# LMP9100_v2_3.net
KiCad netlist of a schematic drawn in EAGLE
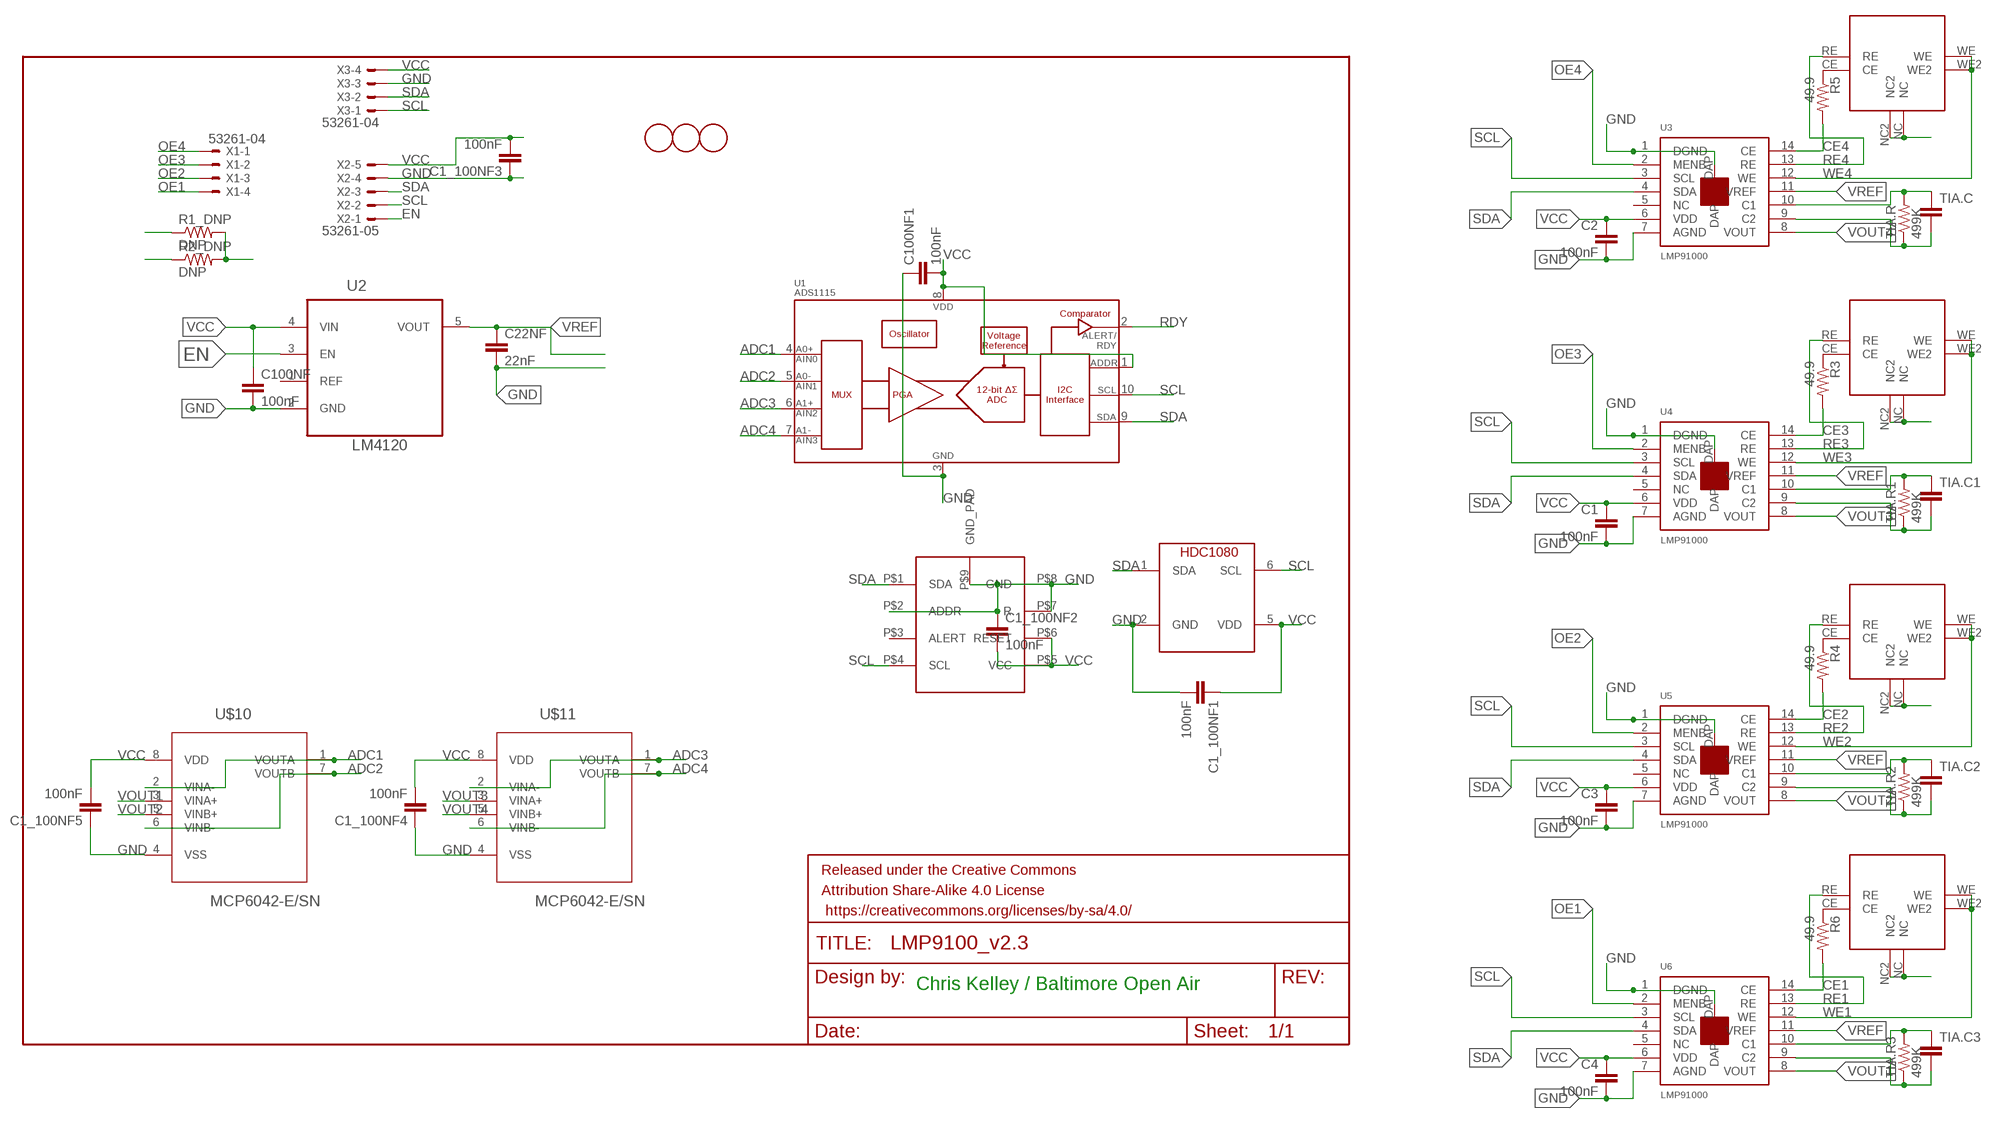
[diagram p0: schematic, sheet 1]

(export (version "E")
  (design (tool "Eeschema 10.0.6"))
  (components
    (comp (ref "C1")
      (value "100nF")
      (footprint "eagle-import:0603-CAP")
      (libsource (lib "eagle-import") (part "CAP0603-CAP"))
    )
    (comp (ref "C1_100NF1")
      (value "100nF")
      (footprint "eagle-import:0603-CAP")
      (libsource (lib "eagle-import") (part "CAP0603-CAP"))
    )
    (comp (ref "C1_100NF2")
      (value "100nF")
      (footprint "eagle-import:0603-CAP")
      (libsource (lib "eagle-import") (part "CAP0603-CAP"))
    )
    (comp (ref "C1_100NF3")
      (value "100nF")
      (footprint "eagle-import:0603-CAP")
      (libsource (lib "eagle-import") (part "CAP0603-CAP"))
    )
    (comp (ref "C1_100NF4")
      (value "100nF")
      (footprint "eagle-import:0603-CAP")
      (libsource (lib "eagle-import") (part "CAP0603-CAP"))
    )
    (comp (ref "C1_100NF5")
      (value "100nF")
      (footprint "eagle-import:0603-CAP")
      (libsource (lib "eagle-import") (part "CAP0603-CAP"))
    )
    (comp (ref "C2")
      (value "100nF")
      (footprint "eagle-import:0603-CAP")
      (libsource (lib "eagle-import") (part "CAP0603-CAP"))
    )
    (comp (ref "C3")
      (value "100nF")
      (footprint "eagle-import:0603-CAP")
      (libsource (lib "eagle-import") (part "CAP0603-CAP"))
    )
    (comp (ref "C4")
      (value "100nF")
      (footprint "eagle-import:0603-CAP")
      (libsource (lib "eagle-import") (part "CAP0603-CAP"))
    )
    (comp (ref "C22NF")
      (value "22nF")
      (footprint "eagle-import:0603-CAP")
      (libsource (lib "eagle-import") (part "CAP0603-CAP"))
    )
    (comp (ref "C100NF")
      (value "100nF")
      (footprint "eagle-import:0603-CAP")
      (libsource (lib "eagle-import") (part "CAP0603-CAP"))
    )
    (comp (ref "C100NF1")
      (value "100nF")
      (footprint "eagle-import:0603-CAP")
      (libsource (lib "eagle-import") (part "CAP0603-CAP"))
    )
    (comp (ref "FRAME1")
      (value "FRAME-LETTER")
      (footprint "eagle-import:CREATIVE_COMMONS")
      (libsource (lib "eagle-import") (part "FRAME-LETTER"))
    )
    (comp (ref "R1_DNP")
      (value "DNP")
      (footprint "eagle-import:0603-RES")
      (libsource (lib "eagle-import") (part "RESISTOR0603-RES"))
    )
    (comp (ref "R2_DNP")
      (value "DNP")
      (footprint "eagle-import:0603-RES")
      (libsource (lib "eagle-import") (part "RESISTOR0603-RES"))
    )
    (comp (ref "R3")
      (value "49.9")
      (footprint "eagle-import:0603-RES")
      (libsource (lib "eagle-import") (part "RESISTOR0603-RES"))
    )
    (comp (ref "R4")
      (value "49.9")
      (footprint "eagle-import:0603-RES")
      (libsource (lib "eagle-import") (part "RESISTOR0603-RES"))
    )
    (comp (ref "R5")
      (value "49.9")
      (footprint "eagle-import:0603-RES")
      (libsource (lib "eagle-import") (part "RESISTOR0603-RES"))
    )
    (comp (ref "R6")
      (value "49.9")
      (footprint "eagle-import:0603-RES")
      (libsource (lib "eagle-import") (part "RESISTOR0603-RES"))
    )
    (comp (ref "TIA.C")
      (value "CAP0603-CAP")
      (footprint "eagle-import:0603-CAP")
      (libsource (lib "eagle-import") (part "CAP0603-CAP"))
    )
    (comp (ref "TIA.C1")
      (value "CAP0603-CAP")
      (footprint "eagle-import:0603-CAP")
      (libsource (lib "eagle-import") (part "CAP0603-CAP"))
    )
    (comp (ref "TIA.C2")
      (value "CAP0603-CAP")
      (footprint "eagle-import:0603-CAP")
      (libsource (lib "eagle-import") (part "CAP0603-CAP"))
    )
    (comp (ref "TIA.C3")
      (value "CAP0603-CAP")
      (footprint "eagle-import:0603-CAP")
      (libsource (lib "eagle-import") (part "CAP0603-CAP"))
    )
    (comp (ref "TIA.R")
      (value "499K")
      (footprint "eagle-import:0603-RES")
      (libsource (lib "eagle-import") (part "RESISTOR0603-RES"))
    )
    (comp (ref "TIA.R1")
      (value "499K")
      (footprint "eagle-import:0603-RES")
      (libsource (lib "eagle-import") (part "RESISTOR0603-RES"))
    )
    (comp (ref "TIA.R2")
      (value "499K")
      (footprint "eagle-import:0603-RES")
      (libsource (lib "eagle-import") (part "RESISTOR0603-RES"))
    )
    (comp (ref "TIA.R3")
      (value "499K")
      (footprint "eagle-import:0603-RES")
      (libsource (lib "eagle-import") (part "RESISTOR0603-RES"))
    )
    (comp (ref "U$1")
      (value "FIDUCIAL")
      (footprint "eagle-import:FIDUCIAL_1MM")
      (libsource (lib "eagle-import") (part "FIDUCIAL"))
    )
    (comp (ref "U$2")
      (value "SHT31-D")
      (footprint "eagle-import:SHT31-D")
      (libsource (lib "eagle-import") (part "SHT31-D"))
    )
    (comp (ref "U$3")
      (value "HDC1080")
      (footprint "eagle-import:WSON-6-PAD")
      (libsource (lib "eagle-import") (part "HDC1080"))
    )
    (comp (ref "U$4")
      (value "SPEC-SENSOR")
      (footprint "eagle-import:SPEC-SENSOR")
      (libsource (lib "eagle-import") (part "SPEC-SENSOR"))
    )
    (comp (ref "U$5")
      (value "SPEC-SENSOR")
      (footprint "eagle-import:SPEC-SENSOR")
      (libsource (lib "eagle-import") (part "SPEC-SENSOR"))
    )
    (comp (ref "U$6")
      (value "FIDUCIAL")
      (footprint "eagle-import:FIDUCIAL_1MM")
      (libsource (lib "eagle-import") (part "FIDUCIAL"))
    )
    (comp (ref "U$7")
      (value "FIDUCIAL")
      (footprint "eagle-import:FIDUCIAL_1MM")
      (libsource (lib "eagle-import") (part "FIDUCIAL"))
    )
    (comp (ref "U$8")
      (value "SPEC-SENSOR")
      (footprint "eagle-import:SPEC-SENSOR")
      (libsource (lib "eagle-import") (part "SPEC-SENSOR"))
    )
    (comp (ref "U$9")
      (value "SPEC-SENSOR")
      (footprint "eagle-import:SPEC-SENSOR")
      (libsource (lib "eagle-import") (part "SPEC-SENSOR"))
    )
    (comp (ref "U$10")
      (value "MCP6042-E/SN")
      (footprint "eagle-import:SOIC127P600X175-8N")
      (fields (field (name "MF") "Microchip"))
      (libsource (lib "eagle-import") (part "MCP6042-E/SN"))
    )
    (comp (ref "U$11")
      (value "MCP6042-E/SN")
      (footprint "eagle-import:SOIC127P600X175-8N")
      (fields (field (name "MF") "Microchip"))
      (libsource (lib "eagle-import") (part "MCP6042-E/SN"))
    )
    (comp (ref "U1")
      (value "ADS1115")
      (footprint "eagle-import:MSOP10")
      (libsource (lib "eagle-import") (part "ADS1015"))
    )
    (comp (ref "U2")
      (value "LM4120")
      (footprint "eagle-import:SOT95P284X122-5N")
      (fields (field (name "MF") "Texas Instruments") (field (name "MP") "LM4120AIM5-2.5/NOPB"))
      (libsource (lib "eagle-import") (part "LM4120AIM5-2.5"))
    )
    (comp (ref "U3")
      (value "LMP91000")
      (footprint "eagle-import:LMP91000")
      (libsource (lib "eagle-import") (part "LMP91000"))
    )
    (comp (ref "U4")
      (value "LMP91000")
      (footprint "eagle-import:LMP91000")
      (libsource (lib "eagle-import") (part "LMP91000"))
    )
    (comp (ref "U5")
      (value "LMP91000")
      (footprint "eagle-import:LMP91000")
      (libsource (lib "eagle-import") (part "LMP91000"))
    )
    (comp (ref "U6")
      (value "LMP91000")
      (footprint "eagle-import:LMP91000")
      (libsource (lib "eagle-import") (part "LMP91000"))
    )
    (comp (ref "X1")
      (value "53261-04")
      (footprint "eagle-import:53261-04")
      (libsource (lib "eagle-import") (part "53?-04261"))
    )
    (comp (ref "X2")
      (value "53261-05")
      (footprint "eagle-import:53261-05")
      (libsource (lib "eagle-import") (part "53?-05261"))
    )
    (comp (ref "X3")
      (value "53261-04")
      (footprint "eagle-import:53261-04")
      (libsource (lib "eagle-import") (part "53?-04261"))
    )
  )
  (nets
    (net (code "1") (name "/ADC1") (class "Default")
      (node (ref "U$10") (pin "1") (pinfunction "VOUTA_1") (pintype "output"))
      (node (ref "U$10") (pin "2") (pinfunction "VINA-_2") (pintype "input"))
      (node (ref "U1") (pin "4") (pinfunction "AIN0_4") (pintype "bidirectional"))
    )
    (net (code "2") (name "/ADC2") (class "Default")
      (node (ref "U$10") (pin "6") (pinfunction "VINB-_6") (pintype "input"))
      (node (ref "U$10") (pin "7") (pinfunction "VOUTB_7") (pintype "output"))
      (node (ref "U1") (pin "5") (pinfunction "AIN1_5") (pintype "bidirectional"))
    )
    (net (code "3") (name "/ADC3") (class "Default")
      (node (ref "U$11") (pin "1") (pinfunction "VOUTA_1") (pintype "output"))
      (node (ref "U$11") (pin "2") (pinfunction "VINA-_2") (pintype "input"))
      (node (ref "U1") (pin "6") (pinfunction "AIN2_6") (pintype "bidirectional"))
    )
    (net (code "4") (name "/ADC4") (class "Default")
      (node (ref "U$11") (pin "6") (pinfunction "VINB-_6") (pintype "input"))
      (node (ref "U$11") (pin "7") (pinfunction "VOUTB_7") (pintype "output"))
      (node (ref "U1") (pin "7") (pinfunction "AIN3_7") (pintype "bidirectional"))
    )
    (net (code "5") (name "/CE1") (class "Default")
      (node (ref "R6") (pin "2") (pinfunction "2_2") (pintype "passive"))
      (node (ref "U6") (pin "14") (pinfunction "CE_14") (pintype "bidirectional"))
    )
    (net (code "6") (name "/CE2") (class "Default")
      (node (ref "R4") (pin "2") (pinfunction "2_2") (pintype "passive"))
      (node (ref "U5") (pin "14") (pinfunction "CE_14") (pintype "bidirectional"))
    )
    (net (code "7") (name "/CE3") (class "Default")
      (node (ref "R3") (pin "2") (pinfunction "2_2") (pintype "passive"))
      (node (ref "U4") (pin "14") (pinfunction "CE_14") (pintype "bidirectional"))
    )
    (net (code "8") (name "/CE4") (class "Default")
      (node (ref "R5") (pin "2") (pinfunction "2_2") (pintype "passive"))
      (node (ref "U3") (pin "14") (pinfunction "CE_14") (pintype "bidirectional"))
    )
    (net (code "9") (name "/RDY") (class "Default")
      (node (ref "U1") (pin "2") (pinfunction "ALERT/RDY_2") (pintype "bidirectional"))
    )
    (net (code "10") (name "/RE1") (class "Default")
      (node (ref "U$9") (pin "RE") (pinfunction "RE_RE") (pintype "bidirectional"))
      (node (ref "U6") (pin "13") (pinfunction "RE_13") (pintype "bidirectional"))
    )
    (net (code "11") (name "/RE2") (class "Default")
      (node (ref "U$8") (pin "RE") (pinfunction "RE_RE") (pintype "bidirectional"))
      (node (ref "U5") (pin "13") (pinfunction "RE_13") (pintype "bidirectional"))
    )
    (net (code "12") (name "/RE3") (class "Default")
      (node (ref "U$5") (pin "RE") (pinfunction "RE_RE") (pintype "bidirectional"))
      (node (ref "U4") (pin "13") (pinfunction "RE_13") (pintype "bidirectional"))
    )
    (net (code "13") (name "/RE4") (class "Default")
      (node (ref "U$4") (pin "RE") (pinfunction "RE_RE") (pintype "bidirectional"))
      (node (ref "U3") (pin "13") (pinfunction "RE_13") (pintype "bidirectional"))
    )
    (net (code "14") (name "/WE1") (class "Default")
      (node (ref "U$9") (pin "WE") (pinfunction "WE_WE") (pintype "bidirectional"))
      (node (ref "U$9") (pin "WE2") (pinfunction "WE2_WE2") (pintype "bidirectional"))
      (node (ref "U6") (pin "12") (pinfunction "WE_12") (pintype "bidirectional"))
    )
    (net (code "15") (name "/WE2") (class "Default")
      (node (ref "U$8") (pin "WE") (pinfunction "WE_WE") (pintype "bidirectional"))
      (node (ref "U$8") (pin "WE2") (pinfunction "WE2_WE2") (pintype "bidirectional"))
      (node (ref "U5") (pin "12") (pinfunction "WE_12") (pintype "bidirectional"))
    )
    (net (code "16") (name "/WE3") (class "Default")
      (node (ref "U$5") (pin "WE") (pinfunction "WE_WE") (pintype "bidirectional"))
      (node (ref "U$5") (pin "WE2") (pinfunction "WE2_WE2") (pintype "bidirectional"))
      (node (ref "U4") (pin "12") (pinfunction "WE_12") (pintype "bidirectional"))
    )
    (net (code "17") (name "/WE4") (class "Default")
      (node (ref "U$4") (pin "WE") (pinfunction "WE_WE") (pintype "bidirectional"))
      (node (ref "U$4") (pin "WE2") (pinfunction "WE2_WE2") (pintype "bidirectional"))
      (node (ref "U3") (pin "12") (pinfunction "WE_12") (pintype "bidirectional"))
    )
    (net (code "18") (name "EN") (class "Default")
      (node (ref "U2") (pin "3") (pinfunction "EN_3") (pintype "input"))
      (node (ref "X2") (pin "1") (pinfunction "S_1") (pintype "passive"))
    )
    (net (code "19") (name "GND") (class "Default")
      (node (ref "C1") (pin "2") (pinfunction "2_2") (pintype "passive"))
      (node (ref "C100NF") (pin "2") (pinfunction "2_2") (pintype "passive"))
      (node (ref "C100NF1") (pin "1") (pinfunction "1_1") (pintype "passive"))
      (node (ref "C1_100NF1") (pin "2") (pinfunction "2_2") (pintype "passive"))
      (node (ref "C1_100NF2") (pin "1") (pinfunction "1_1") (pintype "passive"))
      (node (ref "C1_100NF3") (pin "1") (pinfunction "1_1") (pintype "passive"))
      (node (ref "C1_100NF4") (pin "1") (pinfunction "1_1") (pintype "passive"))
      (node (ref "C1_100NF5") (pin "1") (pinfunction "1_1") (pintype "passive"))
      (node (ref "C2") (pin "2") (pinfunction "2_2") (pintype "passive"))
      (node (ref "C22NF") (pin "2") (pinfunction "2_2") (pintype "passive"))
      (node (ref "C3") (pin "2") (pinfunction "2_2") (pintype "passive"))
      (node (ref "C4") (pin "2") (pinfunction "2_2") (pintype "passive"))
      (node (ref "U$10") (pin "4") (pinfunction "VSS_4") (pintype "power_in"))
      (node (ref "U$11") (pin "4") (pinfunction "VSS_4") (pintype "power_in"))
      (node (ref "U$2") (pin "P$2") (pinfunction "ADDR_P$2") (pintype "bidirectional"))
      (node (ref "U$2") (pin "P$7") (pinfunction "R_P$7") (pintype "bidirectional"))
      (node (ref "U$2") (pin "P$8") (pinfunction "GND_P$8") (pintype "bidirectional"))
      (node (ref "U$2") (pin "P$9") (pinfunction "GND_PAD_P$9") (pintype "bidirectional"))
      (node (ref "U$3") (pin "2") (pinfunction "GND_2") (pintype "bidirectional"))
      (node (ref "U$4") (pin "NC") (pinfunction "NC_NC") (pintype "bidirectional"))
      (node (ref "U$4") (pin "NC2") (pinfunction "NC2_NC2") (pintype "bidirectional"))
      (node (ref "U$5") (pin "NC") (pinfunction "NC_NC") (pintype "bidirectional"))
      (node (ref "U$5") (pin "NC2") (pinfunction "NC2_NC2") (pintype "bidirectional"))
      (node (ref "U$8") (pin "NC") (pinfunction "NC_NC") (pintype "bidirectional"))
      (node (ref "U$8") (pin "NC2") (pinfunction "NC2_NC2") (pintype "bidirectional"))
      (node (ref "U$9") (pin "NC") (pinfunction "NC_NC") (pintype "bidirectional"))
      (node (ref "U$9") (pin "NC2") (pinfunction "NC2_NC2") (pintype "bidirectional"))
      (node (ref "U1") (pin "3") (pinfunction "VSS_3") (pintype "bidirectional"))
      (node (ref "U2") (pin "2") (pinfunction "GND_2") (pintype "passive"))
      (node (ref "U3") (pin "1") (pinfunction "DGND_1") (pintype "bidirectional"))
      (node (ref "U3") (pin "7") (pinfunction "AGND_7") (pintype "bidirectional"))
      (node (ref "U3") (pin "DAP") (pinfunction "DAP_DAP") (pintype "bidirectional"))
      (node (ref "U4") (pin "1") (pinfunction "DGND_1") (pintype "bidirectional"))
      (node (ref "U4") (pin "7") (pinfunction "AGND_7") (pintype "bidirectional"))
      (node (ref "U4") (pin "DAP") (pinfunction "DAP_DAP") (pintype "bidirectional"))
      (node (ref "U5") (pin "1") (pinfunction "DGND_1") (pintype "bidirectional"))
      (node (ref "U5") (pin "7") (pinfunction "AGND_7") (pintype "bidirectional"))
      (node (ref "U5") (pin "DAP") (pinfunction "DAP_DAP") (pintype "bidirectional"))
      (node (ref "U6") (pin "1") (pinfunction "DGND_1") (pintype "bidirectional"))
      (node (ref "U6") (pin "7") (pinfunction "AGND_7") (pintype "bidirectional"))
      (node (ref "U6") (pin "DAP") (pinfunction "DAP_DAP") (pintype "bidirectional"))
      (node (ref "X2") (pin "4") (pinfunction "S_4") (pintype "passive"))
      (node (ref "X3") (pin "3") (pinfunction "S_3") (pintype "passive"))
    )
    (net (code "20") (name "Net-(R3-Pad1)") (class "Default")
      (node (ref "R3") (pin "1") (pinfunction "1_1") (pintype "passive"))
      (node (ref "U$5") (pin "CE") (pinfunction "CE_CE") (pintype "bidirectional"))
    )
    (net (code "21") (name "Net-(R4-Pad1)") (class "Default")
      (node (ref "R4") (pin "1") (pinfunction "1_1") (pintype "passive"))
      (node (ref "U$8") (pin "CE") (pinfunction "CE_CE") (pintype "bidirectional"))
    )
    (net (code "22") (name "Net-(R5-Pad1)") (class "Default")
      (node (ref "R5") (pin "1") (pinfunction "1_1") (pintype "passive"))
      (node (ref "U$4") (pin "CE") (pinfunction "CE_CE") (pintype "bidirectional"))
    )
    (net (code "23") (name "Net-(R6-Pad1)") (class "Default")
      (node (ref "R6") (pin "1") (pinfunction "1_1") (pintype "passive"))
      (node (ref "U$9") (pin "CE") (pinfunction "CE_CE") (pintype "bidirectional"))
    )
    (net (code "24") (name "Net-(U3-C1)") (class "Default")
      (node (ref "TIA.C") (pin "1") (pinfunction "1_1") (pintype "passive"))
      (node (ref "TIA.R") (pin "2") (pinfunction "2_2") (pintype "passive"))
      (node (ref "U3") (pin "10") (pinfunction "C1_10") (pintype "bidirectional"))
    )
    (net (code "25") (name "Net-(U3-C2)") (class "Default")
      (node (ref "TIA.C") (pin "2") (pinfunction "2_2") (pintype "passive"))
      (node (ref "TIA.R") (pin "1") (pinfunction "1_1") (pintype "passive"))
      (node (ref "U3") (pin "9") (pinfunction "C2_9") (pintype "bidirectional"))
    )
    (net (code "26") (name "Net-(U4-C1)") (class "Default")
      (node (ref "TIA.C1") (pin "1") (pinfunction "1_1") (pintype "passive"))
      (node (ref "TIA.R1") (pin "2") (pinfunction "2_2") (pintype "passive"))
      (node (ref "U4") (pin "10") (pinfunction "C1_10") (pintype "bidirectional"))
    )
    (net (code "27") (name "Net-(U4-C2)") (class "Default")
      (node (ref "TIA.C1") (pin "2") (pinfunction "2_2") (pintype "passive"))
      (node (ref "TIA.R1") (pin "1") (pinfunction "1_1") (pintype "passive"))
      (node (ref "U4") (pin "9") (pinfunction "C2_9") (pintype "bidirectional"))
    )
    (net (code "28") (name "Net-(U5-C1)") (class "Default")
      (node (ref "TIA.C2") (pin "1") (pinfunction "1_1") (pintype "passive"))
      (node (ref "TIA.R2") (pin "2") (pinfunction "2_2") (pintype "passive"))
      (node (ref "U5") (pin "10") (pinfunction "C1_10") (pintype "bidirectional"))
    )
    (net (code "29") (name "Net-(U5-C2)") (class "Default")
      (node (ref "TIA.C2") (pin "2") (pinfunction "2_2") (pintype "passive"))
      (node (ref "TIA.R2") (pin "1") (pinfunction "1_1") (pintype "passive"))
      (node (ref "U5") (pin "9") (pinfunction "C2_9") (pintype "bidirectional"))
    )
    (net (code "30") (name "Net-(U6-C1)") (class "Default")
      (node (ref "TIA.C3") (pin "1") (pinfunction "1_1") (pintype "passive"))
      (node (ref "TIA.R3") (pin "2") (pinfunction "2_2") (pintype "passive"))
      (node (ref "U6") (pin "10") (pinfunction "C1_10") (pintype "bidirectional"))
    )
    (net (code "31") (name "Net-(U6-C2)") (class "Default")
      (node (ref "TIA.C3") (pin "2") (pinfunction "2_2") (pintype "passive"))
      (node (ref "TIA.R3") (pin "1") (pinfunction "1_1") (pintype "passive"))
      (node (ref "U6") (pin "9") (pinfunction "C2_9") (pintype "bidirectional"))
    )
    (net (code "32") (name "OE1") (class "Default")
      (node (ref "U6") (pin "2") (pinfunction "MENB_2") (pintype "bidirectional"))
      (node (ref "X1") (pin "4") (pinfunction "S_4") (pintype "passive"))
    )
    (net (code "33") (name "OE2") (class "Default")
      (node (ref "U5") (pin "2") (pinfunction "MENB_2") (pintype "bidirectional"))
      (node (ref "X1") (pin "3") (pinfunction "S_3") (pintype "passive"))
    )
    (net (code "34") (name "OE3") (class "Default")
      (node (ref "U4") (pin "2") (pinfunction "MENB_2") (pintype "bidirectional"))
      (node (ref "X1") (pin "2") (pinfunction "S_2") (pintype "passive"))
    )
    (net (code "35") (name "OE4") (class "Default")
      (node (ref "U3") (pin "2") (pinfunction "MENB_2") (pintype "bidirectional"))
      (node (ref "X1") (pin "1") (pinfunction "S_1") (pintype "passive"))
    )
    (net (code "36") (name "SCL") (class "Default")
      (node (ref "R1_DNP") (pin "1") (pinfunction "1_1") (pintype "passive"))
      (node (ref "U$2") (pin "P$4") (pinfunction "SCL_P$4") (pintype "bidirectional"))
      (node (ref "U$3") (pin "6") (pinfunction "SCL_6") (pintype "bidirectional"))
      (node (ref "U1") (pin "10") (pinfunction "SCL_10") (pintype "bidirectional"))
      (node (ref "U3") (pin "3") (pinfunction "SCL_3") (pintype "bidirectional"))
      (node (ref "U4") (pin "3") (pinfunction "SCL_3") (pintype "bidirectional"))
      (node (ref "U5") (pin "3") (pinfunction "SCL_3") (pintype "bidirectional"))
      (node (ref "U6") (pin "3") (pinfunction "SCL_3") (pintype "bidirectional"))
      (node (ref "X2") (pin "2") (pinfunction "S_2") (pintype "passive"))
      (node (ref "X3") (pin "1") (pinfunction "S_1") (pintype "passive"))
    )
    (net (code "37") (name "SDA") (class "Default")
      (node (ref "R2_DNP") (pin "1") (pinfunction "1_1") (pintype "passive"))
      (node (ref "U$2") (pin "P$1") (pinfunction "SDA_P$1") (pintype "bidirectional"))
      (node (ref "U$3") (pin "1") (pinfunction "SDA_1") (pintype "bidirectional"))
      (node (ref "U1") (pin "9") (pinfunction "SDA_9") (pintype "bidirectional"))
      (node (ref "U3") (pin "4") (pinfunction "SDA_4") (pintype "bidirectional"))
      (node (ref "U4") (pin "4") (pinfunction "SDA_4") (pintype "bidirectional"))
      (node (ref "U5") (pin "4") (pinfunction "SDA_4") (pintype "bidirectional"))
      (node (ref "U6") (pin "4") (pinfunction "SDA_4") (pintype "bidirectional"))
      (node (ref "X2") (pin "3") (pinfunction "S_3") (pintype "passive"))
      (node (ref "X3") (pin "2") (pinfunction "S_2") (pintype "passive"))
    )
    (net (code "38") (name "VCC") (class "Default")
      (node (ref "C1") (pin "1") (pinfunction "1_1") (pintype "passive"))
      (node (ref "C100NF") (pin "1") (pinfunction "1_1") (pintype "passive"))
      (node (ref "C100NF1") (pin "2") (pinfunction "2_2") (pintype "passive"))
      (node (ref "C1_100NF1") (pin "1") (pinfunction "1_1") (pintype "passive"))
      (node (ref "C1_100NF2") (pin "2") (pinfunction "2_2") (pintype "passive"))
      (node (ref "C1_100NF3") (pin "2") (pinfunction "2_2") (pintype "passive"))
      (node (ref "C1_100NF4") (pin "2") (pinfunction "2_2") (pintype "passive"))
      (node (ref "C1_100NF5") (pin "2") (pinfunction "2_2") (pintype "passive"))
      (node (ref "C2") (pin "1") (pinfunction "1_1") (pintype "passive"))
      (node (ref "C3") (pin "1") (pinfunction "1_1") (pintype "passive"))
      (node (ref "C4") (pin "1") (pinfunction "1_1") (pintype "passive"))
      (node (ref "R1_DNP") (pin "2") (pinfunction "2_2") (pintype "passive"))
      (node (ref "R2_DNP") (pin "2") (pinfunction "2_2") (pintype "passive"))
      (node (ref "U$10") (pin "8") (pinfunction "VDD_8") (pintype "power_in"))
      (node (ref "U$11") (pin "8") (pinfunction "VDD_8") (pintype "power_in"))
      (node (ref "U$2") (pin "P$5") (pinfunction "VCC_P$5") (pintype "bidirectional"))
      (node (ref "U$2") (pin "P$6") (pinfunction "RESET_P$6") (pintype "bidirectional"))
      (node (ref "U$3") (pin "5") (pinfunction "VDD_5") (pintype "bidirectional"))
      (node (ref "U1") (pin "1") (pinfunction "ADDR_1") (pintype "bidirectional"))
      (node (ref "U1") (pin "8") (pinfunction "VDD_8") (pintype "bidirectional"))
      (node (ref "U2") (pin "4") (pinfunction "VIN_4") (pintype "input"))
      (node (ref "U3") (pin "6") (pinfunction "VDD_6") (pintype "bidirectional"))
      (node (ref "U4") (pin "6") (pinfunction "VDD_6") (pintype "bidirectional"))
      (node (ref "U5") (pin "6") (pinfunction "VDD_6") (pintype "bidirectional"))
      (node (ref "U6") (pin "6") (pinfunction "VDD_6") (pintype "bidirectional"))
      (node (ref "X2") (pin "5") (pinfunction "S_5") (pintype "passive"))
      (node (ref "X3") (pin "4") (pinfunction "S_4") (pintype "passive"))
    )
    (net (code "39") (name "VOUT1") (class "Default")
      (node (ref "U$10") (pin "3") (pinfunction "VINA+_3") (pintype "input"))
      (node (ref "U6") (pin "8") (pinfunction "VOUT_8") (pintype "bidirectional"))
    )
    (net (code "40") (name "VOUT2") (class "Default")
      (node (ref "U$10") (pin "5") (pinfunction "VINB+_5") (pintype "input"))
      (node (ref "U5") (pin "8") (pinfunction "VOUT_8") (pintype "bidirectional"))
    )
    (net (code "41") (name "VOUT3") (class "Default")
      (node (ref "U$11") (pin "3") (pinfunction "VINA+_3") (pintype "input"))
      (node (ref "U4") (pin "8") (pinfunction "VOUT_8") (pintype "bidirectional"))
    )
    (net (code "42") (name "VOUT4") (class "Default")
      (node (ref "U$11") (pin "5") (pinfunction "VINB+_5") (pintype "input"))
      (node (ref "U3") (pin "8") (pinfunction "VOUT_8") (pintype "bidirectional"))
    )
    (net (code "43") (name "VREF") (class "Default")
      (node (ref "C22NF") (pin "1") (pinfunction "1_1") (pintype "passive"))
      (node (ref "U2") (pin "5") (pinfunction "VOUT_5") (pintype "output"))
      (node (ref "U3") (pin "11") (pinfunction "VREF_11") (pintype "bidirectional"))
      (node (ref "U4") (pin "11") (pinfunction "VREF_11") (pintype "bidirectional"))
      (node (ref "U5") (pin "11") (pinfunction "VREF_11") (pintype "bidirectional"))
      (node (ref "U6") (pin "11") (pinfunction "VREF_11") (pintype "bidirectional"))
    )
    (net (code "44") (name "unconnected-(U$2-ALERT-PadP$3)") (class "Default")
      (node (ref "U$2") (pin "P$3") (pinfunction "ALERT_P$3") (pintype "bidirectional"))
    )
    (net (code "45") (name "unconnected-(U2-REF-Pad1)") (class "Default")
      (node (ref "U2") (pin "1") (pinfunction "REF_1") (pintype "passive"))
    )
    (net (code "46") (name "unconnected-(U3-NC-Pad5)") (class "Default")
      (node (ref "U3") (pin "5") (pinfunction "NC_5") (pintype "bidirectional"))
    )
    (net (code "47") (name "unconnected-(U4-NC-Pad5)") (class "Default")
      (node (ref "U4") (pin "5") (pinfunction "NC_5") (pintype "bidirectional"))
    )
    (net (code "48") (name "unconnected-(U5-NC-Pad5)") (class "Default")
      (node (ref "U5") (pin "5") (pinfunction "NC_5") (pintype "bidirectional"))
    )
    (net (code "49") (name "unconnected-(U6-NC-Pad5)") (class "Default")
      (node (ref "U6") (pin "5") (pinfunction "NC_5") (pintype "bidirectional"))
    )
  )
)
